# Sweep_Oscillator.net
KiCad netlist of a schematic drawn in Altium Designer
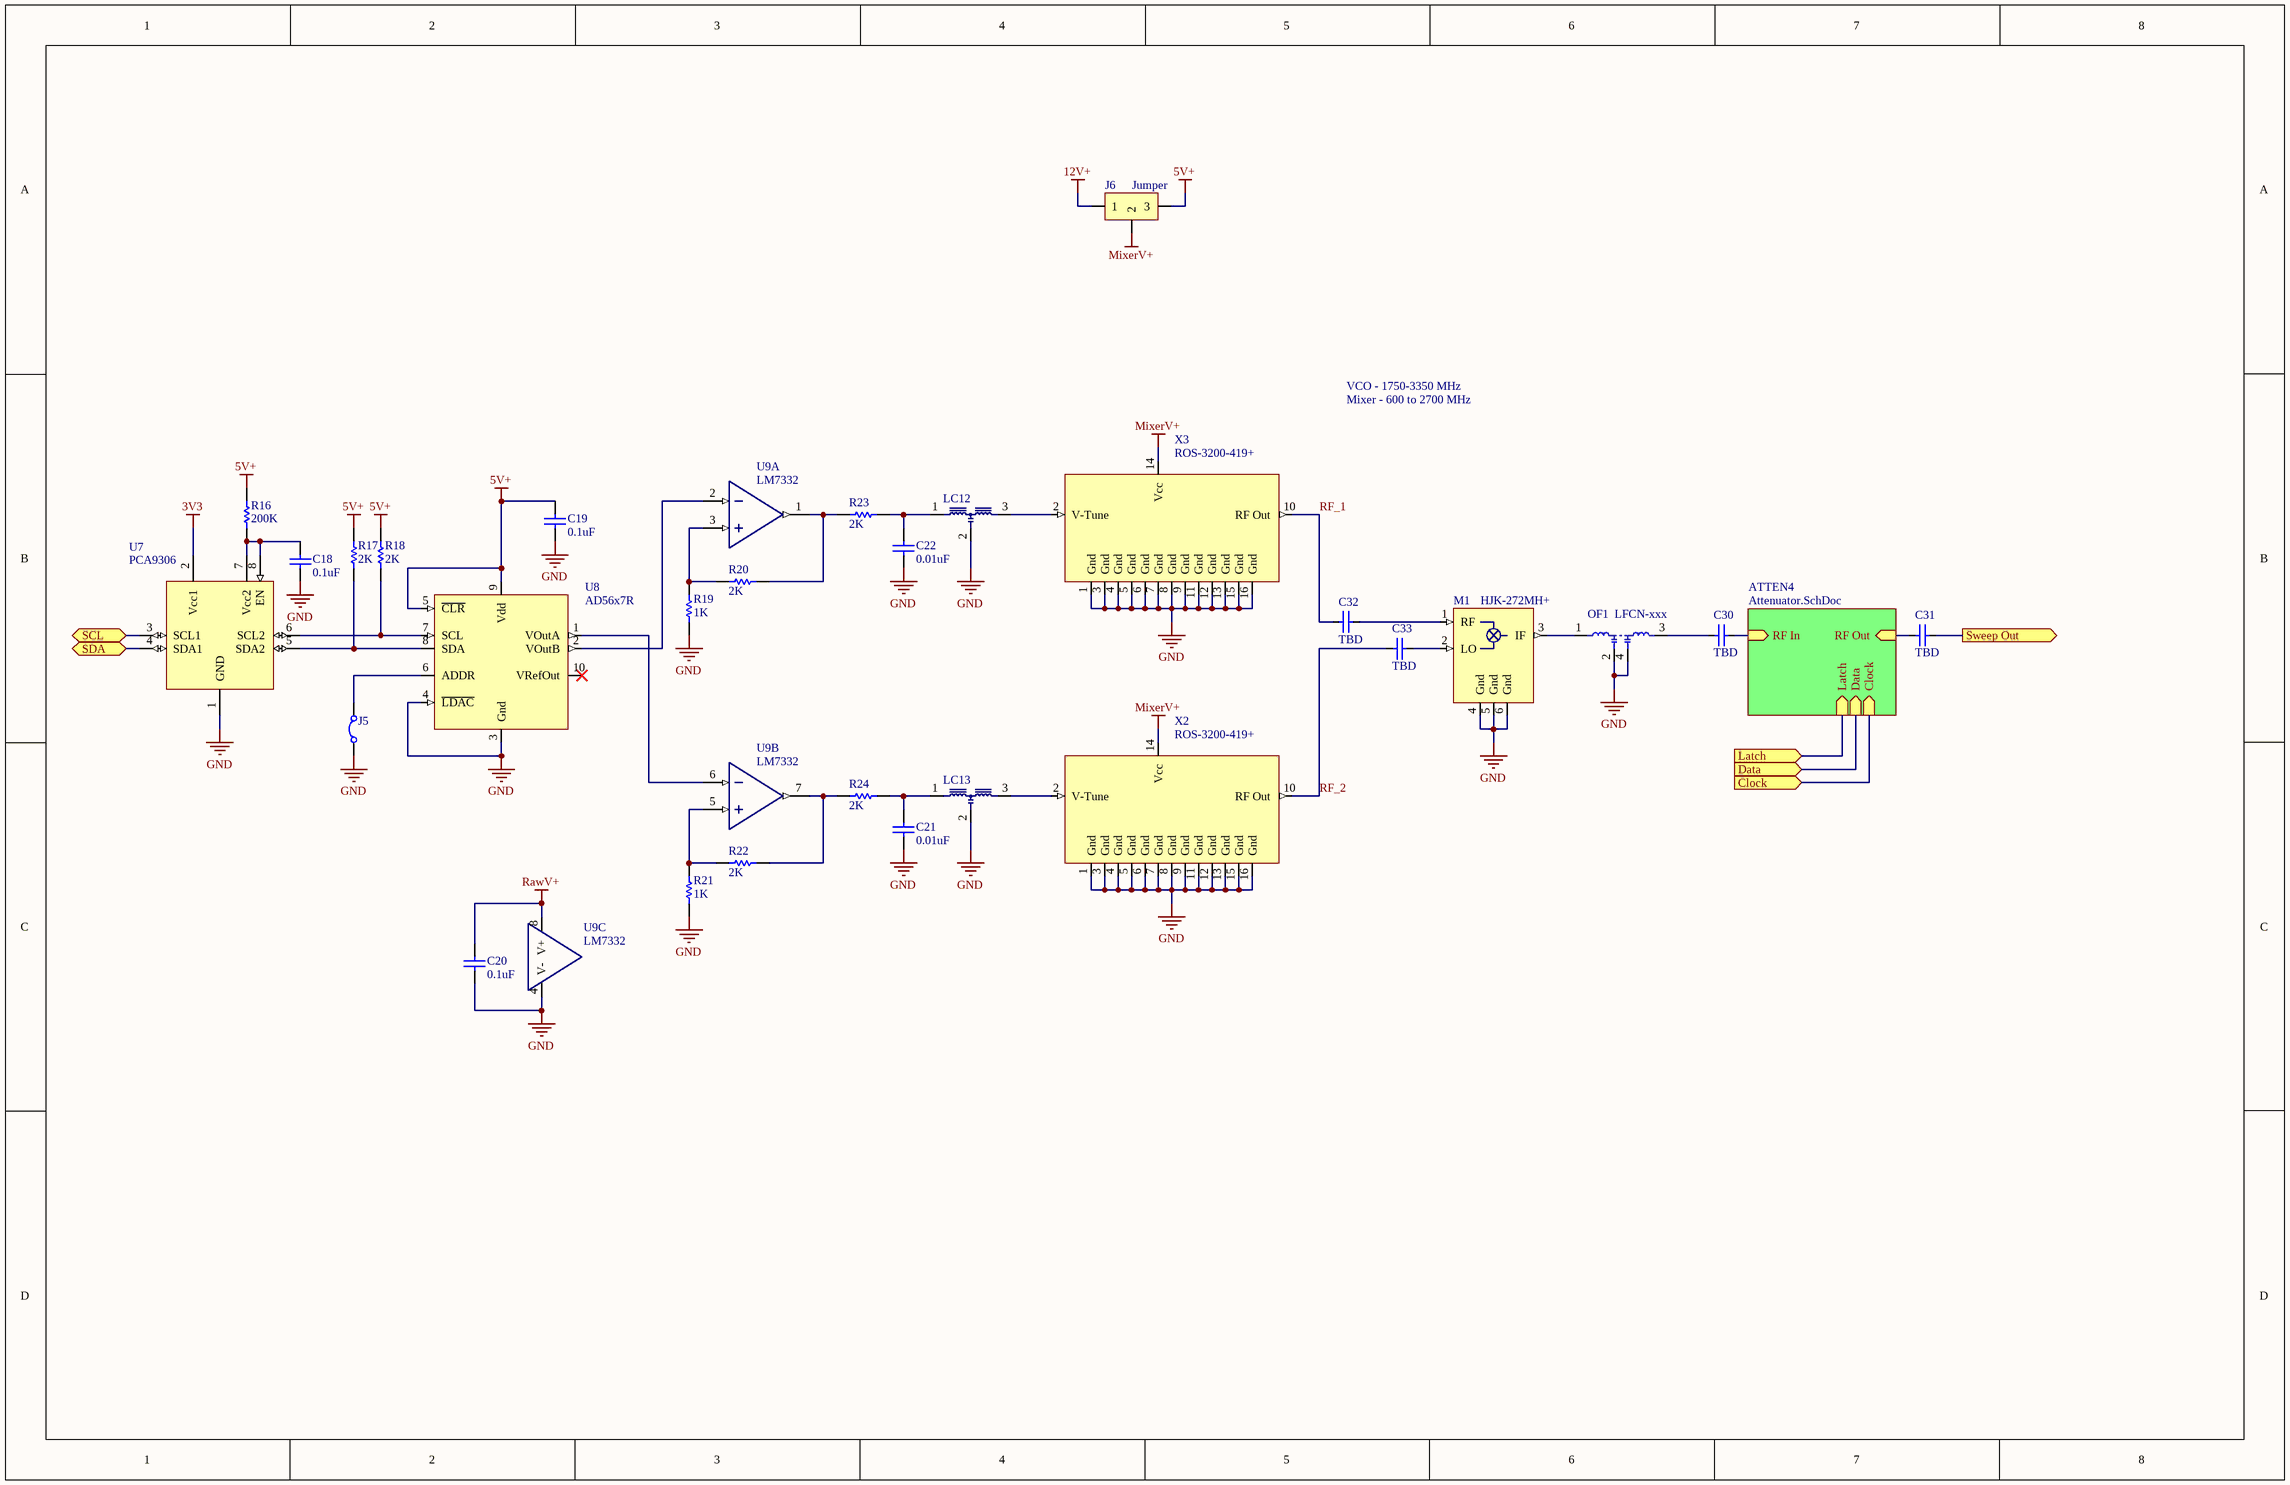
[diagram p0: Sweep Oscillator.SchDoc]

(export (version "E")
  (design (tool "Eeschema 10.0.6"))
  (components
    (comp (ref "C18")
      (value "0.1uF")
      (footprint "0603C")
      (description "Capacitor (Semiconductor SIM Model)")
      (fields (field (name "Comment") "Cap Semi") (field (name "PUBLISHER") "Altium Limited"))
      (libsource (lib "Miscellaneous Devices") (part "Cap Semi"))
    )
    (comp (ref "C19")
      (value "0.1uF")
      (footprint "0603C")
      (description "Capacitor (Semiconductor SIM Model)")
      (fields (field (name "Comment") "Cap Semi") (field (name "PUBLISHER") "Altium Limited"))
      (libsource (lib "Miscellaneous Devices") (part "Cap Semi"))
    )
    (comp (ref "C20")
      (value "0.1uF")
      (footprint "0603C")
      (description "Capacitor (Semiconductor SIM Model)")
      (fields (field (name "Comment") "Cap Semi") (field (name "PUBLISHER") "Altium Limited"))
      (libsource (lib "Miscellaneous Devices") (part "Cap Semi"))
    )
    (comp (ref "C21")
      (value "0.01uF")
      (footprint "0603C")
      (description "Capacitor (Semiconductor SIM Model)")
      (fields (field (name "Comment") "Cap Semi") (field (name "PUBLISHER") "Altium Limited"))
      (libsource (lib "Miscellaneous Devices") (part "Cap Semi"))
    )
    (comp (ref "C22")
      (value "0.01uF")
      (footprint "0603C")
      (description "Capacitor (Semiconductor SIM Model)")
      (fields (field (name "Comment") "Cap Semi") (field (name "PUBLISHER") "Altium Limited"))
      (libsource (lib "Miscellaneous Devices") (part "Cap Semi"))
    )
    (comp (ref "C30")
      (value "TBD")
      (footprint "0402C")
      (description "Capacitor")
      (fields (field (name "Comment") "Cap") (field (name "PUBLISHER") "Altium Limited"))
      (libsource (lib "Miscellaneous Devices") (part "Cap"))
    )
    (comp (ref "C31")
      (value "TBD")
      (footprint "0402C")
      (description "Capacitor")
      (fields (field (name "Comment") "Cap") (field (name "PUBLISHER") "Altium Limited"))
      (libsource (lib "Miscellaneous Devices") (part "Cap"))
    )
    (comp (ref "C32")
      (value "TBD")
      (footprint "0402C")
      (description "Capacitor")
      (fields (field (name "Comment") "Cap") (field (name "PUBLISHER") "Altium Limited"))
      (libsource (lib "Miscellaneous Devices") (part "Cap"))
    )
    (comp (ref "C33")
      (value "TBD")
      (footprint "0402C")
      (description "Capacitor")
      (fields (field (name "Comment") "Cap") (field (name "PUBLISHER") "Altium Limited"))
      (libsource (lib "Miscellaneous Devices") (part "Cap"))
    )
    (comp (ref "J5")
      (value "~")
      (footprint "0603R")
      (libsource (lib "Miscellaneous Devices") (part "Jumper - SMT Resistor"))
    )
    (comp (ref "J6")
      (value "Jumper")
      (footprint "HDR1X3")
      (description "Jumper - 3-Pin")
      (fields (field (name "PUBLISHER") "Altium Limited"))
      (libsource (lib "Miscellaneous Connectors") (part "Jumper - 3 Pin"))
    )
    (comp (ref "LC12")
      (value "MEM2012F")
      (footprint "MEM2012S LC Filter")
      (description "Signal Line 3-terminal Filters")
      (libsource (lib "Unsorted") (part "MEM2012F - Signal Filter"))
    )
    (comp (ref "LC13")
      (value "MEM2012F")
      (footprint "MEM2012S LC Filter")
      (description "Signal Line 3-terminal Filters")
      (libsource (lib "Unsorted") (part "MEM2012F - Signal Filter"))
    )
    (comp (ref "M1")
      (value "HJK-272MH+")
      (footprint "TTT881")
      (description "Wideband Frequency Mixer Level 13 (LO Power +13 dBm) 600 to 2700 MHz")
      (libsource (lib "RF Components") (part "HJK-272MH+"))
    )
    (comp (ref "OF1")
      (value "LFCN-xxx")
      (footprint "FV1206")
      (description "Ceramic Low Pass Filter")
      (libsource (lib "RF Components") (part "LFCN-xxx Filter"))
    )
    (comp (ref "R16")
      (value "200K")
      (footprint "0603R")
      (description "Semiconductor Resistor")
      (fields (field (name "Comment") "Res Semi") (field (name "PUBLISHER") "Altium Limited"))
      (libsource (lib "Miscellaneous Devices") (part "Res Semi"))
    )
    (comp (ref "R17")
      (value "2K")
      (footprint "0603R")
      (description "Semiconductor Resistor")
      (fields (field (name "Comment") "Res Semi") (field (name "PUBLISHER") "Altium Limited"))
      (libsource (lib "Miscellaneous Devices") (part "Res Semi"))
    )
    (comp (ref "R18")
      (value "2K")
      (footprint "0603R")
      (description "Semiconductor Resistor")
      (fields (field (name "Comment") "Res Semi") (field (name "PUBLISHER") "Altium Limited"))
      (libsource (lib "Miscellaneous Devices") (part "Res Semi"))
    )
    (comp (ref "R19")
      (value "1K")
      (footprint "0603R")
      (description "Semiconductor Resistor")
      (fields (field (name "Comment") "Res Semi") (field (name "PUBLISHER") "Altium Limited"))
      (libsource (lib "Miscellaneous Devices") (part "Res Semi"))
    )
    (comp (ref "R20")
      (value "2K")
      (footprint "0603R")
      (description "Semiconductor Resistor")
      (fields (field (name "Comment") "Res Semi") (field (name "PUBLISHER") "Altium Limited"))
      (libsource (lib "Miscellaneous Devices") (part "Res Semi"))
    )
    (comp (ref "R21")
      (value "1K")
      (footprint "0603R")
      (description "Semiconductor Resistor")
      (fields (field (name "Comment") "Res Semi") (field (name "PUBLISHER") "Altium Limited"))
      (libsource (lib "Miscellaneous Devices") (part "Res Semi"))
    )
    (comp (ref "R22")
      (value "2K")
      (footprint "0603R")
      (description "Semiconductor Resistor")
      (fields (field (name "Comment") "Res Semi") (field (name "PUBLISHER") "Altium Limited"))
      (libsource (lib "Miscellaneous Devices") (part "Res Semi"))
    )
    (comp (ref "R23")
      (value "2K")
      (footprint "0603R")
      (description "Semiconductor Resistor")
      (fields (field (name "Comment") "Res Semi") (field (name "PUBLISHER") "Altium Limited"))
      (libsource (lib "Miscellaneous Devices") (part "Res Semi"))
    )
    (comp (ref "R24")
      (value "2K")
      (footprint "0603R")
      (description "Semiconductor Resistor")
      (fields (field (name "Comment") "Res Semi") (field (name "PUBLISHER") "Altium Limited"))
      (libsource (lib "Miscellaneous Devices") (part "Res Semi"))
    )
    (comp (ref "U7")
      (value "PCA9306")
      (footprint "TSOP65P490-8AN")
      (description "Dual bidirectional I2C-bus and SMBus voltage-level translator")
      (libsource (lib "ICs") (part "PCA9306"))
    )
    (comp (ref "U8")
      (value "AD56x7R")
      (footprint "TSSOP50P490-10AN")
      (description "Dual, 12-/14-/16-Bit nanoDACs® with  5 ppm/°C On-Chip Reference, I2C Interface")
      (libsource (lib "ICs") (part "AD56x7R"))
    )
    (comp (ref "U9")
      (value "LM7332")
      (footprint "SOIC127P600-8CN")
      (description "Dual Rail-to-Rail Input/Output, 30V, Wide Voltage Range, High Output Operational Amplifier")
      (libsource (lib "ICs") (part "LM7332"))
    )
    (comp (ref "X2")
      (value "ROS-3200-419+")
      (footprint "CK605")
      (description "Linear Tuning 2165 to 2650 MHz SMT Voltage Controlled Oscillator")
      (libsource (lib "RF Components") (part "ROS-2650 VCO"))
    )
    (comp (ref "X3")
      (value "ROS-3200-419+")
      (footprint "CK605")
      (description "Linear Tuning 2165 to 2650 MHz SMT Voltage Controlled Oscillator")
      (libsource (lib "RF Components") (part "ROS-2650 VCO"))
    )
  )
  (nets
    (net (code "4") (name "/RF In") (class "Default")
      (node (ref "C30") (pin "2") (pinfunction "2_2") (pintype "passive"))
    )
    (net (code "5") (name "/RF Out") (class "Default")
      (node (ref "C31") (pin "1") (pinfunction "1_1") (pintype "passive"))
    )
    (net (code "6") (name "/RF_1") (class "Default")
      (node (ref "C32") (pin "1") (pinfunction "1_1") (pintype "passive"))
      (node (ref "X3") (pin "10") (pinfunction "RF_Out_10") (pintype "output"))
    )
    (net (code "7") (name "/RF_2") (class "Default")
      (node (ref "C33") (pin "1") (pinfunction "1_1") (pintype "passive"))
      (node (ref "X2") (pin "10") (pinfunction "RF_Out_10") (pintype "output"))
    )
    (net (code "8") (name "/SCL") (class "Default")
      (node (ref "U7") (pin "3") (pinfunction "SCL1_3") (pintype "bidirectional"))
    )
    (net (code "9") (name "/SDA") (class "Default")
      (node (ref "U7") (pin "4") (pinfunction "SDA1_4") (pintype "bidirectional"))
    )
    (net (code "10") (name "/Sweep Out") (class "Default")
      (node (ref "C31") (pin "2") (pinfunction "2_2") (pintype "passive"))
    )
    (net (code "11") (name "3V3") (class "Default")
      (node (ref "U7") (pin "2") (pinfunction "Vcc1_2") (pintype "power_in"))
    )
    (net (code "12") (name "5V+") (class "Default")
      (node (ref "C19") (pin "2") (pinfunction "2_2") (pintype "passive"))
      (node (ref "J6") (pin "3") (pinfunction "3_3") (pintype "passive"))
      (node (ref "R16") (pin "2") (pinfunction "2_2") (pintype "passive"))
      (node (ref "R17") (pin "2") (pinfunction "2_2") (pintype "passive"))
      (node (ref "R18") (pin "2") (pinfunction "2_2") (pintype "passive"))
      (node (ref "U8") (pin "5") (pinfunction "CLR_5") (pintype "input"))
      (node (ref "U8") (pin "9") (pinfunction "Vdd_9") (pintype "power_in"))
    )
    (net (code "13") (name "12V+") (class "Default")
      (node (ref "J6") (pin "1") (pinfunction "1_1") (pintype "passive"))
    )
    (net (code "14") (name "GND") (class "Default")
      (node (ref "C18") (pin "1") (pinfunction "1_1") (pintype "passive"))
      (node (ref "C19") (pin "1") (pinfunction "1_1") (pintype "passive"))
      (node (ref "C20") (pin "1") (pinfunction "1_1") (pintype "passive"))
      (node (ref "C21") (pin "1") (pinfunction "1_1") (pintype "passive"))
      (node (ref "C22") (pin "1") (pinfunction "1_1") (pintype "passive"))
      (node (ref "J5") (pin "1") (pinfunction "C1_1") (pintype "passive"))
      (node (ref "LC12") (pin "2") (pinfunction "2_2") (pintype "passive"))
      (node (ref "LC13") (pin "2") (pinfunction "2_2") (pintype "passive"))
      (node (ref "M1") (pin "4") (pinfunction "Gnd_4") (pintype "power_in"))
      (node (ref "M1") (pin "5") (pinfunction "Gnd_5") (pintype "power_in"))
      (node (ref "M1") (pin "6") (pinfunction "Gnd_6") (pintype "power_in"))
      (node (ref "OF1") (pin "2") (pintype "passive"))
      (node (ref "OF1") (pin "4") (pintype "passive"))
      (node (ref "R19") (pin "2") (pinfunction "2_2") (pintype "passive"))
      (node (ref "R21") (pin "1") (pinfunction "1_1") (pintype "passive"))
      (node (ref "U7") (pin "1") (pinfunction "GND_1") (pintype "power_in"))
      (node (ref "U8") (pin "3") (pinfunction "Gnd_3") (pintype "power_in"))
      (node (ref "U8") (pin "4") (pinfunction "LDAC_4") (pintype "input"))
      (node (ref "U9") (pin "4") (pinfunction "V-_4") (pintype "power_in"))
      (node (ref "X2") (pin "1") (pinfunction "Gnd_1") (pintype "power_in"))
      (node (ref "X2") (pin "11") (pinfunction "Gnd_11") (pintype "power_in"))
      (node (ref "X2") (pin "12") (pinfunction "Gnd_12") (pintype "power_in"))
      (node (ref "X2") (pin "13") (pinfunction "Gnd_13") (pintype "power_in"))
      (node (ref "X2") (pin "15") (pinfunction "Gnd_15") (pintype "power_in"))
      (node (ref "X2") (pin "16") (pinfunction "Gnd_16") (pintype "power_in"))
      (node (ref "X2") (pin "3") (pinfunction "Gnd_3") (pintype "power_in"))
      (node (ref "X2") (pin "4") (pinfunction "Gnd_4") (pintype "power_in"))
      (node (ref "X2") (pin "5") (pinfunction "Gnd_5") (pintype "power_in"))
      (node (ref "X2") (pin "6") (pinfunction "Gnd_6") (pintype "power_in"))
      (node (ref "X2") (pin "7") (pinfunction "Gnd_7") (pintype "power_in"))
      (node (ref "X2") (pin "8") (pinfunction "Gnd_8") (pintype "power_in"))
      (node (ref "X2") (pin "9") (pinfunction "Gnd_9") (pintype "power_in"))
      (node (ref "X3") (pin "1") (pinfunction "Gnd_1") (pintype "power_in"))
      (node (ref "X3") (pin "11") (pinfunction "Gnd_11") (pintype "power_in"))
      (node (ref "X3") (pin "12") (pinfunction "Gnd_12") (pintype "power_in"))
      (node (ref "X3") (pin "13") (pinfunction "Gnd_13") (pintype "power_in"))
      (node (ref "X3") (pin "15") (pinfunction "Gnd_15") (pintype "power_in"))
      (node (ref "X3") (pin "16") (pinfunction "Gnd_16") (pintype "power_in"))
      (node (ref "X3") (pin "3") (pinfunction "Gnd_3") (pintype "power_in"))
      (node (ref "X3") (pin "4") (pinfunction "Gnd_4") (pintype "power_in"))
      (node (ref "X3") (pin "5") (pinfunction "Gnd_5") (pintype "power_in"))
      (node (ref "X3") (pin "6") (pinfunction "Gnd_6") (pintype "power_in"))
      (node (ref "X3") (pin "7") (pinfunction "Gnd_7") (pintype "power_in"))
      (node (ref "X3") (pin "8") (pinfunction "Gnd_8") (pintype "power_in"))
      (node (ref "X3") (pin "9") (pinfunction "Gnd_9") (pintype "power_in"))
    )
    (net (code "15") (name "MixerV+") (class "Default")
      (node (ref "J6") (pin "2") (pinfunction "2_2") (pintype "passive"))
      (node (ref "X2") (pin "14") (pinfunction "Vcc_14") (pintype "power_in"))
      (node (ref "X3") (pin "14") (pinfunction "Vcc_14") (pintype "power_in"))
    )
    (net (code "16") (name "Net-(C21-Pad2)") (class "Default")
      (node (ref "C21") (pin "2") (pinfunction "2_2") (pintype "passive"))
      (node (ref "LC13") (pin "1") (pinfunction "1_1") (pintype "passive"))
      (node (ref "R24") (pin "1") (pinfunction "1_1") (pintype "passive"))
    )
    (net (code "17") (name "Net-(C22-Pad2)") (class "Default")
      (node (ref "C22") (pin "2") (pinfunction "2_2") (pintype "passive"))
      (node (ref "LC12") (pin "1") (pinfunction "1_1") (pintype "passive"))
      (node (ref "R23") (pin "1") (pinfunction "1_1") (pintype "passive"))
    )
    (net (code "18") (name "Net-(C30-Pad1)") (class "Default")
      (node (ref "C30") (pin "1") (pinfunction "1_1") (pintype "passive"))
      (node (ref "OF1") (pin "3") (pintype "passive"))
    )
    (net (code "19") (name "Net-(J5-C2)") (class "Default")
      (node (ref "J5") (pin "2") (pinfunction "C2_2") (pintype "passive"))
      (node (ref "U8") (pin "6") (pinfunction "ADDR_6") (pintype "passive"))
    )
    (net (code "20") (name "Net-(M1-IF)") (class "Default")
      (node (ref "M1") (pin "3") (pinfunction "IF_3") (pintype "output"))
      (node (ref "OF1") (pin "1") (pintype "passive"))
    )
    (net (code "21") (name "Net-(M1-LO)") (class "Default")
      (node (ref "C33") (pin "2") (pinfunction "2_2") (pintype "passive"))
      (node (ref "M1") (pin "2") (pinfunction "LO_2") (pintype "input"))
    )
    (net (code "22") (name "Net-(M1-RF)") (class "Default")
      (node (ref "C32") (pin "2") (pinfunction "2_2") (pintype "passive"))
      (node (ref "M1") (pin "1") (pinfunction "RF_1") (pintype "input"))
    )
    (net (code "23") (name "Net-(U7-EN)") (class "Default")
      (node (ref "C18") (pin "2") (pinfunction "2_2") (pintype "passive"))
      (node (ref "R16") (pin "1") (pinfunction "1_1") (pintype "passive"))
      (node (ref "U7") (pin "7") (pinfunction "Vcc2_7") (pintype "power_in"))
      (node (ref "U7") (pin "8") (pinfunction "EN_8") (pintype "input"))
    )
    (net (code "24") (name "Net-(U7-SCL2)") (class "Default")
      (node (ref "R18") (pin "1") (pinfunction "1_1") (pintype "passive"))
      (node (ref "U7") (pin "6") (pinfunction "SCL2_6") (pintype "bidirectional"))
      (node (ref "U8") (pin "7") (pinfunction "SCL_7") (pintype "input"))
    )
    (net (code "25") (name "Net-(U7-SDA2)") (class "Default")
      (node (ref "R17") (pin "1") (pinfunction "1_1") (pintype "passive"))
      (node (ref "U7") (pin "5") (pinfunction "SDA2_5") (pintype "bidirectional"))
      (node (ref "U8") (pin "8") (pinfunction "SDA_8") (pintype "bidirectional"))
    )
    (net (code "26") (name "Net-(U8-VOutA)") (class "Default")
      (node (ref "U8") (pin "1") (pinfunction "VOutA_1") (pintype "output"))
      (node (ref "U9") (pin "6") (pinfunction "In_B_-_6") (pintype "input"))
    )
    (net (code "27") (name "Net-(U8-VOutB)") (class "Default")
      (node (ref "U8") (pin "2") (pinfunction "VOutB_2") (pintype "output"))
      (node (ref "U9") (pin "2") (pinfunction "In_A_-_2") (pintype "input"))
    )
    (net (code "28") (name "Net-(U9A-In_A_+)") (class "Default")
      (node (ref "R19") (pin "1") (pinfunction "1_1") (pintype "passive"))
      (node (ref "R20") (pin "1") (pinfunction "1_1") (pintype "passive"))
      (node (ref "U9") (pin "3") (pinfunction "In_A_+_3") (pintype "input"))
    )
    (net (code "29") (name "Net-(U9A-Out_A)") (class "Default")
      (node (ref "R20") (pin "2") (pinfunction "2_2") (pintype "passive"))
      (node (ref "R23") (pin "2") (pinfunction "2_2") (pintype "passive"))
      (node (ref "U9") (pin "1") (pinfunction "Out_A_1") (pintype "output"))
    )
    (net (code "30") (name "Net-(U9B-In_B_+)") (class "Default")
      (node (ref "R21") (pin "2") (pinfunction "2_2") (pintype "passive"))
      (node (ref "R22") (pin "2") (pinfunction "2_2") (pintype "passive"))
      (node (ref "U9") (pin "5") (pinfunction "In_B_+_5") (pintype "input"))
    )
    (net (code "31") (name "Net-(U9B-Out_B)") (class "Default")
      (node (ref "R22") (pin "1") (pinfunction "1_1") (pintype "passive"))
      (node (ref "R24") (pin "2") (pinfunction "2_2") (pintype "passive"))
      (node (ref "U9") (pin "7") (pinfunction "Out_B_7") (pintype "output"))
    )
    (net (code "32") (name "Net-(X2-V-Tune)") (class "Default")
      (node (ref "LC13") (pin "3") (pinfunction "3_3") (pintype "passive"))
      (node (ref "X2") (pin "2") (pinfunction "V-Tune_2") (pintype "input"))
    )
    (net (code "33") (name "Net-(X3-V-Tune)") (class "Default")
      (node (ref "LC12") (pin "3") (pinfunction "3_3") (pintype "passive"))
      (node (ref "X3") (pin "2") (pinfunction "V-Tune_2") (pintype "input"))
    )
    (net (code "34") (name "RawV+") (class "Default")
      (node (ref "C20") (pin "2") (pinfunction "2_2") (pintype "passive"))
      (node (ref "U9") (pin "8") (pinfunction "V+_8") (pintype "power_in"))
    )
    (net (code "35") (name "unconnected-(U8-VRefOut-Pad10)") (class "Default")
      (node (ref "U8") (pin "10") (pinfunction "VRefOut_10") (pintype "power_in+no_connect"))
    )
  )
)
